# Noduino-iBaihe.net
KiCad netlist of a schematic drawn in EAGLE
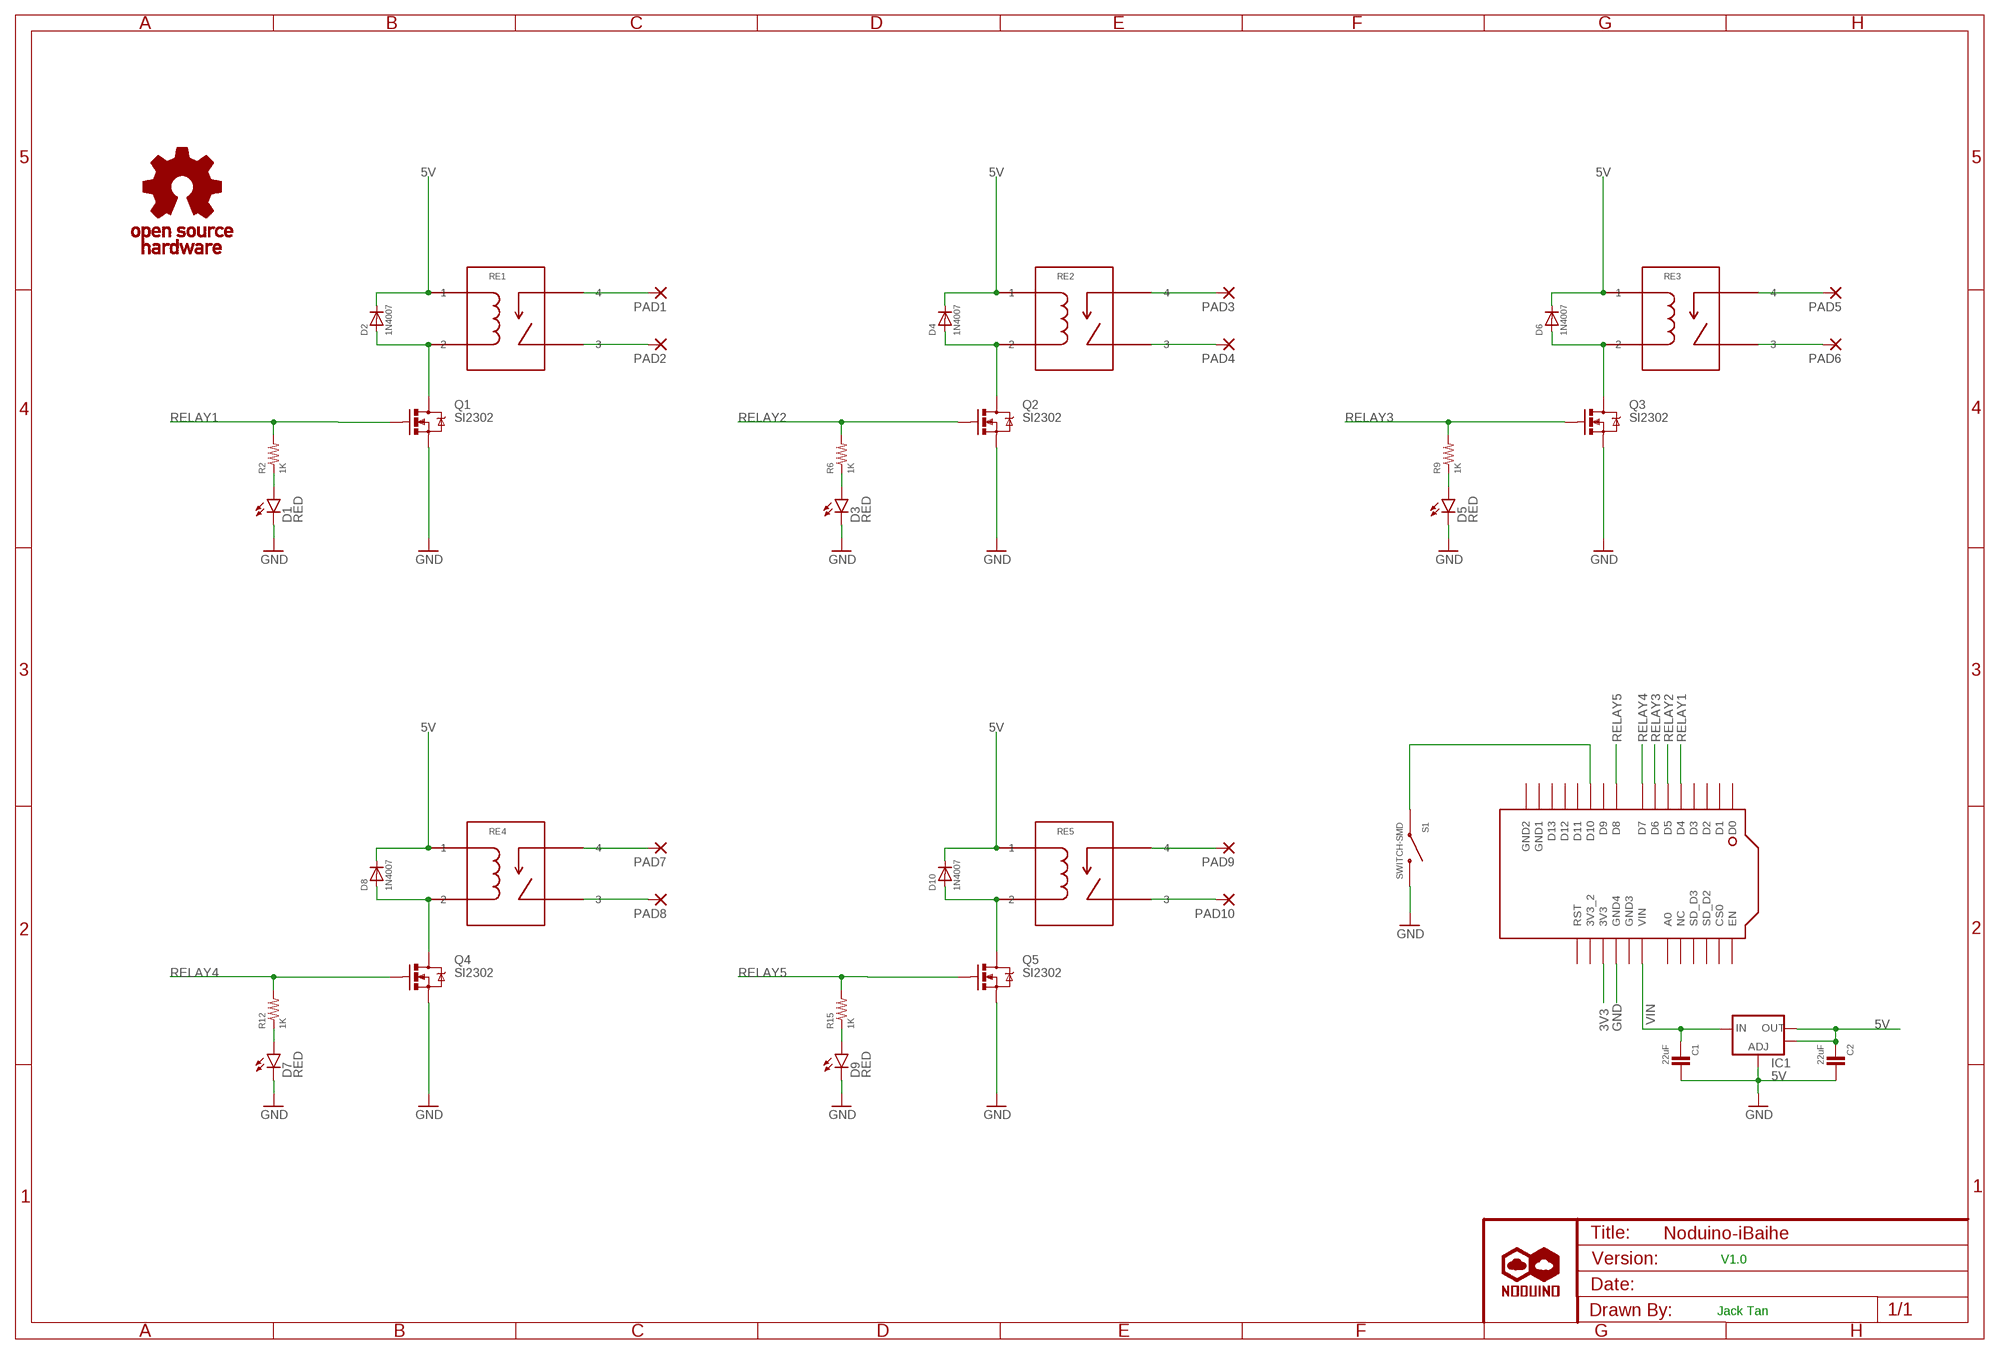
[diagram p0: schematic, sheet 1]

(export (version "E")
  (design (tool "Eeschema 10.0.6"))
  (components
    (comp (ref "C1")
      (value "22uF")
      (footprint "eagle-import:C1206")
      (libsource (lib "eagle-import") (part "1206-CAP"))
    )
    (comp (ref "C2")
      (value "22uF")
      (footprint "eagle-import:C1206")
      (libsource (lib "eagle-import") (part "1206-CAP"))
    )
    (comp (ref "D1")
      (value "RED")
      (footprint "eagle-import:LED-0603")
      (libsource (lib "eagle-import") (part "LED-RED0603"))
    )
    (comp (ref "D2")
      (value "1N4007")
      (footprint "eagle-import:SOD-323")
      (libsource (lib "eagle-import") (part "DIODESOD"))
    )
    (comp (ref "D3")
      (value "RED")
      (footprint "eagle-import:LED-0603")
      (libsource (lib "eagle-import") (part "LED-RED0603"))
    )
    (comp (ref "D4")
      (value "1N4007")
      (footprint "eagle-import:SOD-323")
      (libsource (lib "eagle-import") (part "DIODESOD"))
    )
    (comp (ref "D5")
      (value "RED")
      (footprint "eagle-import:LED-0603")
      (libsource (lib "eagle-import") (part "LED-RED0603"))
    )
    (comp (ref "D6")
      (value "1N4007")
      (footprint "eagle-import:SOD-323")
      (libsource (lib "eagle-import") (part "DIODESOD"))
    )
    (comp (ref "D7")
      (value "RED")
      (footprint "eagle-import:LED-0603")
      (libsource (lib "eagle-import") (part "LED-RED0603"))
    )
    (comp (ref "D8")
      (value "1N4007")
      (footprint "eagle-import:SOD-323")
      (libsource (lib "eagle-import") (part "DIODESOD"))
    )
    (comp (ref "D9")
      (value "RED")
      (footprint "eagle-import:LED-0603")
      (libsource (lib "eagle-import") (part "LED-RED0603"))
    )
    (comp (ref "D10")
      (value "1N4007")
      (footprint "eagle-import:SOD-323")
      (libsource (lib "eagle-import") (part "DIODESOD"))
    )
    (comp (ref "IC1")
      (value "5V")
      (footprint "eagle-import:SOT223")
      (libsource (lib "eagle-import") (part "AMS1117SOT223"))
    )
    (comp (ref "N1")
      (value "NODUINO-PINMAIL")
      (footprint "eagle-import:NODUINO-PIN-MAIL")
      (libsource (lib "eagle-import") (part "NODUINO-PINMAIL"))
    )
    (comp (ref "PAD1")
      (value "2,15/1,0")
      (footprint "eagle-import:2,15_1,0")
      (libsource (lib "eagle-import") (part "2,15/1,0"))
    )
    (comp (ref "PAD2")
      (value "2,15/1,0")
      (footprint "eagle-import:2,15_1,0")
      (libsource (lib "eagle-import") (part "2,15/1,0"))
    )
    (comp (ref "PAD3")
      (value "2,15/1,0")
      (footprint "eagle-import:2,15_1,0")
      (libsource (lib "eagle-import") (part "2,15/1,0"))
    )
    (comp (ref "PAD4")
      (value "2,15/1,0")
      (footprint "eagle-import:2,15_1,0")
      (libsource (lib "eagle-import") (part "2,15/1,0"))
    )
    (comp (ref "PAD5")
      (value "2,15/1,0")
      (footprint "eagle-import:2,15_1,0")
      (libsource (lib "eagle-import") (part "2,15/1,0"))
    )
    (comp (ref "PAD6")
      (value "2,15/1,0")
      (footprint "eagle-import:2,15_1,0")
      (libsource (lib "eagle-import") (part "2,15/1,0"))
    )
    (comp (ref "PAD7")
      (value "2,15/1,0")
      (footprint "eagle-import:2,15_1,0")
      (libsource (lib "eagle-import") (part "2,15/1,0"))
    )
    (comp (ref "PAD8")
      (value "2,15/1,0")
      (footprint "eagle-import:2,15_1,0")
      (libsource (lib "eagle-import") (part "2,15/1,0"))
    )
    (comp (ref "PAD9")
      (value "2,15/1,0")
      (footprint "eagle-import:2,15_1,0")
      (libsource (lib "eagle-import") (part "2,15/1,0"))
    )
    (comp (ref "PAD10")
      (value "2,15/1,0")
      (footprint "eagle-import:2,15_1,0")
      (libsource (lib "eagle-import") (part "2,15/1,0"))
    )
    (comp (ref "Q1")
      (value "SI2302")
      (footprint "eagle-import:SOT23-3")
      (libsource (lib "eagle-import") (part "MOSFET-N-SMD"))
    )
    (comp (ref "Q2")
      (value "SI2302")
      (footprint "eagle-import:SOT23-3")
      (libsource (lib "eagle-import") (part "MOSFET-N-SMD"))
    )
    (comp (ref "Q3")
      (value "SI2302")
      (footprint "eagle-import:SOT23-3")
      (libsource (lib "eagle-import") (part "MOSFET-N-SMD"))
    )
    (comp (ref "Q4")
      (value "SI2302")
      (footprint "eagle-import:SOT23-3")
      (libsource (lib "eagle-import") (part "MOSFET-N-SMD"))
    )
    (comp (ref "Q5")
      (value "SI2302")
      (footprint "eagle-import:SOT23-3")
      (libsource (lib "eagle-import") (part "MOSFET-N-SMD"))
    )
    (comp (ref "R2")
      (value "1K")
      (footprint "eagle-import:0603-RES")
      (libsource (lib "eagle-import") (part "0603-RESISTOR"))
    )
    (comp (ref "R6")
      (value "1K")
      (footprint "eagle-import:0603-RES")
      (libsource (lib "eagle-import") (part "0603-RESISTOR"))
    )
    (comp (ref "R9")
      (value "1K")
      (footprint "eagle-import:0603-RES")
      (libsource (lib "eagle-import") (part "0603-RESISTOR"))
    )
    (comp (ref "R12")
      (value "1K")
      (footprint "eagle-import:0603-RES")
      (libsource (lib "eagle-import") (part "0603-RESISTOR"))
    )
    (comp (ref "R15")
      (value "1K")
      (footprint "eagle-import:0603-RES")
      (libsource (lib "eagle-import") (part "0603-RESISTOR"))
    )
    (comp (ref "RE1")
      (value "HKE-HRS3FNH")
      (footprint "eagle-import:HKE-HRS3FN")
      (libsource (lib "eagle-import") (part "HKE-HRS3FNH"))
    )
    (comp (ref "RE2")
      (value "HKE-HRS3FNH")
      (footprint "eagle-import:HKE-HRS3FN")
      (libsource (lib "eagle-import") (part "HKE-HRS3FNH"))
    )
    (comp (ref "RE3")
      (value "HKE-HRS3FNH")
      (footprint "eagle-import:HKE-HRS3FN")
      (libsource (lib "eagle-import") (part "HKE-HRS3FNH"))
    )
    (comp (ref "RE4")
      (value "HKE-HRS3FNH")
      (footprint "eagle-import:HKE-HRS3FN")
      (libsource (lib "eagle-import") (part "HKE-HRS3FNH"))
    )
    (comp (ref "RE5")
      (value "HKE-HRS3FNH")
      (footprint "eagle-import:HKE-HRS3FN")
      (libsource (lib "eagle-import") (part "HKE-HRS3FNH"))
    )
    (comp (ref "S1")
      (value "SWITCH-SMD")
      (footprint "eagle-import:TACTILE-SWITCH-1101NE")
      (libsource (lib "eagle-import") (part "SWITCH-SMD"))
    )
    (comp (ref "U$1")
      (value "NODUINO-LOGO-ALL")
      (footprint "eagle-import:NODUINO-ALL-1")
      (libsource (lib "eagle-import") (part "NODUINO-LOGO-ALL"))
    )
    (comp (ref "U$2")
      (value "OPEN_HARDWARE_LOGO")
      (footprint "eagle-import:OPEN_HARDWARE_LOGO")
      (libsource (lib "eagle-import") (part "OPEN_HARDWARE_LOGO"))
    )
  )
  (nets
    (net (code "1") (name "/3V3") (class "Default")
      (node (ref "N1") (pin "P$26") (pinfunction "3V3_P$26") (pintype "bidirectional"))
    )
    (net (code "2") (name "/5V") (class "Default")
      (node (ref "C2") (pin "1") (pinfunction "1_1") (pintype "passive"))
      (node (ref "D10") (pin "1") (pinfunction "C_1") (pintype "passive"))
      (node (ref "D2") (pin "1") (pinfunction "C_1") (pintype "passive"))
      (node (ref "D4") (pin "1") (pinfunction "C_1") (pintype "passive"))
      (node (ref "D6") (pin "1") (pinfunction "C_1") (pintype "passive"))
      (node (ref "D8") (pin "1") (pinfunction "C_1") (pintype "passive"))
      (node (ref "IC1") (pin "2") (pinfunction "OUT_2") (pintype "bidirectional"))
      (node (ref "IC1") (pin "4") (pinfunction "OUT_4") (pintype "bidirectional"))
      (node (ref "RE1") (pin "1") (pinfunction "1_1") (pintype "bidirectional"))
      (node (ref "RE2") (pin "1") (pinfunction "1_1") (pintype "bidirectional"))
      (node (ref "RE3") (pin "1") (pinfunction "1_1") (pintype "bidirectional"))
      (node (ref "RE4") (pin "1") (pinfunction "1_1") (pintype "bidirectional"))
      (node (ref "RE5") (pin "1") (pinfunction "1_1") (pintype "bidirectional"))
    )
    (net (code "3") (name "/RELAY1") (class "Default")
      (node (ref "N1") (pin "P$5") (pinfunction "D4_P$5") (pintype "bidirectional"))
      (node (ref "Q1") (pin "1") (pinfunction "G_1") (pintype "passive"))
      (node (ref "R2") (pin "2") (pinfunction "2_2") (pintype "passive"))
    )
    (net (code "4") (name "/RELAY2") (class "Default")
      (node (ref "N1") (pin "P$6") (pinfunction "D5_P$6") (pintype "bidirectional"))
      (node (ref "Q2") (pin "1") (pinfunction "G_1") (pintype "passive"))
      (node (ref "R6") (pin "2") (pinfunction "2_2") (pintype "passive"))
    )
    (net (code "5") (name "/RELAY3") (class "Default")
      (node (ref "N1") (pin "P$7") (pinfunction "D6_P$7") (pintype "bidirectional"))
      (node (ref "Q3") (pin "1") (pinfunction "G_1") (pintype "passive"))
      (node (ref "R9") (pin "2") (pinfunction "2_2") (pintype "passive"))
    )
    (net (code "6") (name "/RELAY4") (class "Default")
      (node (ref "N1") (pin "P$8") (pinfunction "D7_P$8") (pintype "bidirectional"))
      (node (ref "Q4") (pin "1") (pinfunction "G_1") (pintype "passive"))
      (node (ref "R12") (pin "2") (pinfunction "2_2") (pintype "passive"))
    )
    (net (code "7") (name "/RELAY5") (class "Default")
      (node (ref "N1") (pin "P$9") (pinfunction "D8_P$9") (pintype "bidirectional"))
      (node (ref "Q5") (pin "1") (pinfunction "G_1") (pintype "passive"))
      (node (ref "R15") (pin "2") (pinfunction "2_2") (pintype "passive"))
    )
    (net (code "8") (name "/VIN") (class "Default")
      (node (ref "C1") (pin "1") (pinfunction "1_1") (pintype "passive"))
      (node (ref "IC1") (pin "3") (pinfunction "IN_3") (pintype "input"))
      (node (ref "N1") (pin "P$23") (pinfunction "VIN_P$23") (pintype "bidirectional"))
    )
    (net (code "9") (name "GND") (class "Default")
      (node (ref "C1") (pin "2") (pinfunction "2_2") (pintype "passive"))
      (node (ref "C2") (pin "2") (pinfunction "2_2") (pintype "passive"))
      (node (ref "D1") (pin "C") (pinfunction "C_C") (pintype "passive"))
      (node (ref "D3") (pin "C") (pinfunction "C_C") (pintype "passive"))
      (node (ref "D5") (pin "C") (pinfunction "C_C") (pintype "passive"))
      (node (ref "D7") (pin "C") (pinfunction "C_C") (pintype "passive"))
      (node (ref "D9") (pin "C") (pinfunction "C_C") (pintype "passive"))
      (node (ref "IC1") (pin "1") (pinfunction "ADJ_1") (pintype "input"))
      (node (ref "N1") (pin "P$25") (pinfunction "GND4_P$25") (pintype "bidirectional"))
      (node (ref "Q1") (pin "2") (pinfunction "S_2") (pintype "passive"))
      (node (ref "Q2") (pin "2") (pinfunction "S_2") (pintype "passive"))
      (node (ref "Q3") (pin "2") (pinfunction "S_2") (pintype "passive"))
      (node (ref "Q4") (pin "2") (pinfunction "S_2") (pintype "passive"))
      (node (ref "Q5") (pin "2") (pinfunction "S_2") (pintype "passive"))
      (node (ref "S1") (pin "P$1") (pinfunction "1_P$1") (pintype "bidirectional"))
    )
    (net (code "10") (name "Net-(D1-PadA)") (class "Default")
      (node (ref "D1") (pin "A") (pinfunction "A_A") (pintype "passive"))
      (node (ref "R2") (pin "1") (pinfunction "1_1") (pintype "passive"))
    )
    (net (code "11") (name "Net-(D2-A)") (class "Default")
      (node (ref "D2") (pin "2") (pinfunction "A_2") (pintype "passive"))
      (node (ref "Q1") (pin "3") (pinfunction "D_3") (pintype "passive"))
      (node (ref "RE1") (pin "2") (pinfunction "2_2") (pintype "bidirectional"))
    )
    (net (code "12") (name "Net-(D3-PadA)") (class "Default")
      (node (ref "D3") (pin "A") (pinfunction "A_A") (pintype "passive"))
      (node (ref "R6") (pin "1") (pinfunction "1_1") (pintype "passive"))
    )
    (net (code "13") (name "Net-(D4-A)") (class "Default")
      (node (ref "D4") (pin "2") (pinfunction "A_2") (pintype "passive"))
      (node (ref "Q2") (pin "3") (pinfunction "D_3") (pintype "passive"))
      (node (ref "RE2") (pin "2") (pinfunction "2_2") (pintype "bidirectional"))
    )
    (net (code "14") (name "Net-(D5-PadA)") (class "Default")
      (node (ref "D5") (pin "A") (pinfunction "A_A") (pintype "passive"))
      (node (ref "R9") (pin "1") (pinfunction "1_1") (pintype "passive"))
    )
    (net (code "15") (name "Net-(D6-A)") (class "Default")
      (node (ref "D6") (pin "2") (pinfunction "A_2") (pintype "passive"))
      (node (ref "Q3") (pin "3") (pinfunction "D_3") (pintype "passive"))
      (node (ref "RE3") (pin "2") (pinfunction "2_2") (pintype "bidirectional"))
    )
    (net (code "16") (name "Net-(D7-PadA)") (class "Default")
      (node (ref "D7") (pin "A") (pinfunction "A_A") (pintype "passive"))
      (node (ref "R12") (pin "1") (pinfunction "1_1") (pintype "passive"))
    )
    (net (code "17") (name "Net-(D8-A)") (class "Default")
      (node (ref "D8") (pin "2") (pinfunction "A_2") (pintype "passive"))
      (node (ref "Q4") (pin "3") (pinfunction "D_3") (pintype "passive"))
      (node (ref "RE4") (pin "2") (pinfunction "2_2") (pintype "bidirectional"))
    )
    (net (code "18") (name "Net-(D9-PadA)") (class "Default")
      (node (ref "D9") (pin "A") (pinfunction "A_A") (pintype "passive"))
      (node (ref "R15") (pin "1") (pinfunction "1_1") (pintype "passive"))
    )
    (net (code "19") (name "Net-(D10-A)") (class "Default")
      (node (ref "D10") (pin "2") (pinfunction "A_2") (pintype "passive"))
      (node (ref "Q5") (pin "3") (pinfunction "D_3") (pintype "passive"))
      (node (ref "RE5") (pin "2") (pinfunction "2_2") (pintype "bidirectional"))
    )
    (net (code "20") (name "Net-(N1-D10)") (class "Default")
      (node (ref "N1") (pin "P$11") (pinfunction "D10_P$11") (pintype "bidirectional"))
      (node (ref "S1") (pin "P$2") (pinfunction "2_P$2") (pintype "bidirectional"))
    )
    (net (code "21") (name "Net-(PAD1-P)") (class "Default")
      (node (ref "PAD1") (pin "1") (pinfunction "P_1") (pintype "passive"))
      (node (ref "RE1") (pin "4") (pinfunction "4_4") (pintype "bidirectional"))
    )
    (net (code "22") (name "Net-(PAD2-P)") (class "Default")
      (node (ref "PAD2") (pin "1") (pinfunction "P_1") (pintype "passive"))
      (node (ref "RE1") (pin "3") (pinfunction "3_3") (pintype "bidirectional"))
    )
    (net (code "23") (name "Net-(PAD3-P)") (class "Default")
      (node (ref "PAD3") (pin "1") (pinfunction "P_1") (pintype "passive"))
      (node (ref "RE2") (pin "4") (pinfunction "4_4") (pintype "bidirectional"))
    )
    (net (code "24") (name "Net-(PAD4-P)") (class "Default")
      (node (ref "PAD4") (pin "1") (pinfunction "P_1") (pintype "passive"))
      (node (ref "RE2") (pin "3") (pinfunction "3_3") (pintype "bidirectional"))
    )
    (net (code "25") (name "Net-(PAD5-P)") (class "Default")
      (node (ref "PAD5") (pin "1") (pinfunction "P_1") (pintype "passive"))
      (node (ref "RE3") (pin "4") (pinfunction "4_4") (pintype "bidirectional"))
    )
    (net (code "26") (name "Net-(PAD6-P)") (class "Default")
      (node (ref "PAD6") (pin "1") (pinfunction "P_1") (pintype "passive"))
      (node (ref "RE3") (pin "3") (pinfunction "3_3") (pintype "bidirectional"))
    )
    (net (code "27") (name "Net-(PAD7-P)") (class "Default")
      (node (ref "PAD7") (pin "1") (pinfunction "P_1") (pintype "passive"))
      (node (ref "RE4") (pin "4") (pinfunction "4_4") (pintype "bidirectional"))
    )
    (net (code "28") (name "Net-(PAD8-P)") (class "Default")
      (node (ref "PAD8") (pin "1") (pinfunction "P_1") (pintype "passive"))
      (node (ref "RE4") (pin "3") (pinfunction "3_3") (pintype "bidirectional"))
    )
    (net (code "29") (name "Net-(PAD9-P)") (class "Default")
      (node (ref "PAD9") (pin "1") (pinfunction "P_1") (pintype "passive"))
      (node (ref "RE5") (pin "4") (pinfunction "4_4") (pintype "bidirectional"))
    )
    (net (code "30") (name "Net-(PAD10-P)") (class "Default")
      (node (ref "PAD10") (pin "1") (pinfunction "P_1") (pintype "passive"))
      (node (ref "RE5") (pin "3") (pinfunction "3_3") (pintype "bidirectional"))
    )
    (net (code "31") (name "unconnected-(N1-3V3_2-PadP$27)") (class "Default")
      (node (ref "N1") (pin "P$27") (pinfunction "3V3_2_P$27") (pintype "bidirectional"))
    )
    (net (code "32") (name "unconnected-(N1-A0-PadP$22)") (class "Default")
      (node (ref "N1") (pin "P$22") (pinfunction "A0_P$22") (pintype "bidirectional"))
    )
    (net (code "33") (name "unconnected-(N1-CS0-PadP$18)") (class "Default")
      (node (ref "N1") (pin "P$18") (pinfunction "CS0_P$18") (pintype "bidirectional"))
    )
    (net (code "34") (name "unconnected-(N1-D0-PadP$1)") (class "Default")
      (node (ref "N1") (pin "P$1") (pinfunction "D0_P$1") (pintype "bidirectional"))
    )
    (net (code "35") (name "unconnected-(N1-D1-PadP$2)") (class "Default")
      (node (ref "N1") (pin "P$2") (pinfunction "D1_P$2") (pintype "bidirectional"))
    )
    (net (code "36") (name "unconnected-(N1-D2-PadP$3)") (class "Default")
      (node (ref "N1") (pin "P$3") (pinfunction "D2_P$3") (pintype "bidirectional"))
    )
    (net (code "37") (name "unconnected-(N1-D3-PadP$4)") (class "Default")
      (node (ref "N1") (pin "P$4") (pinfunction "D3_P$4") (pintype "bidirectional"))
    )
    (net (code "38") (name "unconnected-(N1-D9-PadP$10)") (class "Default")
      (node (ref "N1") (pin "P$10") (pinfunction "D9_P$10") (pintype "bidirectional"))
    )
    (net (code "39") (name "unconnected-(N1-D11-PadP$12)") (class "Default")
      (node (ref "N1") (pin "P$12") (pinfunction "D11_P$12") (pintype "bidirectional"))
    )
    (net (code "40") (name "unconnected-(N1-D12-PadP$13)") (class "Default")
      (node (ref "N1") (pin "P$13") (pinfunction "D12_P$13") (pintype "bidirectional"))
    )
    (net (code "41") (name "unconnected-(N1-D13-PadP$14)") (class "Default")
      (node (ref "N1") (pin "P$14") (pinfunction "D13_P$14") (pintype "bidirectional"))
    )
    (net (code "42") (name "unconnected-(N1-EN-PadP$17)") (class "Default")
      (node (ref "N1") (pin "P$17") (pinfunction "EN_P$17") (pintype "bidirectional"))
    )
    (net (code "43") (name "unconnected-(N1-GND1-PadP$15)") (class "Default")
      (node (ref "N1") (pin "P$15") (pinfunction "GND1_P$15") (pintype "bidirectional"))
    )
    (net (code "44") (name "unconnected-(N1-GND2-PadP$16)") (class "Default")
      (node (ref "N1") (pin "P$16") (pinfunction "GND2_P$16") (pintype "bidirectional"))
    )
    (net (code "45") (name "unconnected-(N1-GND3-PadP$24)") (class "Default")
      (node (ref "N1") (pin "P$24") (pinfunction "GND3_P$24") (pintype "bidirectional"))
    )
    (net (code "46") (name "unconnected-(N1-NC-PadP$21)") (class "Default")
      (node (ref "N1") (pin "P$21") (pinfunction "NC_P$21") (pintype "bidirectional"))
    )
    (net (code "47") (name "unconnected-(N1-RST-PadP$28)") (class "Default")
      (node (ref "N1") (pin "P$28") (pinfunction "RST_P$28") (pintype "bidirectional"))
    )
    (net (code "48") (name "unconnected-(N1-SD_D2-PadP$19)") (class "Default")
      (node (ref "N1") (pin "P$19") (pinfunction "SD_D2_P$19") (pintype "bidirectional"))
    )
    (net (code "49") (name "unconnected-(N1-SD_D3-PadP$20)") (class "Default")
      (node (ref "N1") (pin "P$20") (pinfunction "SD_D3_P$20") (pintype "bidirectional"))
    )
  )
)
